# mosfet.net
KiCad netlist of a schematic drawn in EAGLE
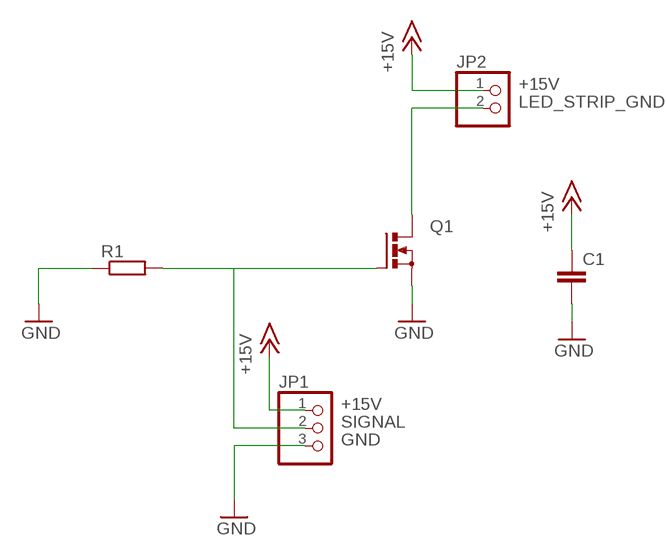
[diagram p0: schematic, sheet 1]

(export (version "E")
  (design (tool "Eeschema 10.0.6"))
  (components
    (comp (ref "C1")
      (value "C-EU050-025X075")
      (footprint "eagle-import:C050-025X075")
      (libsource (lib "eagle-import") (part "C-EU050-025X075"))
    )
    (comp (ref "JP1")
      (value "PINHD-1X3")
      (footprint "eagle-import:1X03")
      (libsource (lib "eagle-import") (part "PINHD-1X3"))
    )
    (comp (ref "JP2")
      (value "PINHD-1X2")
      (footprint "eagle-import:1X02")
      (libsource (lib "eagle-import") (part "PINHD-1X2"))
    )
    (comp (ref "Q1")
      (value "PMOSFET_NTO220BV")
      (footprint "eagle-import:TO220BV")
      (libsource (lib "eagle-import") (part "PMOSFET_NTO220BV"))
    )
    (comp (ref "R1")
      (value "R-EU_M0805")
      (footprint "eagle-import:M0805")
      (libsource (lib "eagle-import") (part "R-EU_M0805"))
    )
  )
  (nets
    (net (code "1") (name "+15V") (class "Default")
      (node (ref "C1") (pin "1") (pinfunction "1_1") (pintype "passive"))
      (node (ref "JP1") (pin "1") (pinfunction "1_1") (pintype "passive"))
      (node (ref "JP2") (pin "1") (pinfunction "1_1") (pintype "passive"))
    )
    (net (code "2") (name "/LED_STRIP_GND") (class "Default")
      (node (ref "JP2") (pin "2") (pinfunction "2_2") (pintype "passive"))
      (node (ref "Q1") (pin "D") (pinfunction "D_D") (pintype "passive"))
    )
    (net (code "3") (name "/SIGNAL") (class "Default")
      (node (ref "JP1") (pin "2") (pinfunction "2_2") (pintype "passive"))
      (node (ref "Q1") (pin "G") (pinfunction "G_G") (pintype "passive"))
      (node (ref "R1") (pin "2") (pinfunction "2_2") (pintype "passive"))
    )
    (net (code "4") (name "GND") (class "Default")
      (node (ref "C1") (pin "2") (pinfunction "2_2") (pintype "passive"))
      (node (ref "JP1") (pin "3") (pinfunction "3_3") (pintype "passive"))
      (node (ref "Q1") (pin "S") (pinfunction "S_S") (pintype "passive"))
      (node (ref "R1") (pin "1") (pinfunction "1_1") (pintype "passive"))
    )
  )
)
